# Dummy_Load.net
KiCad netlist of a schematic drawn in EAGLE
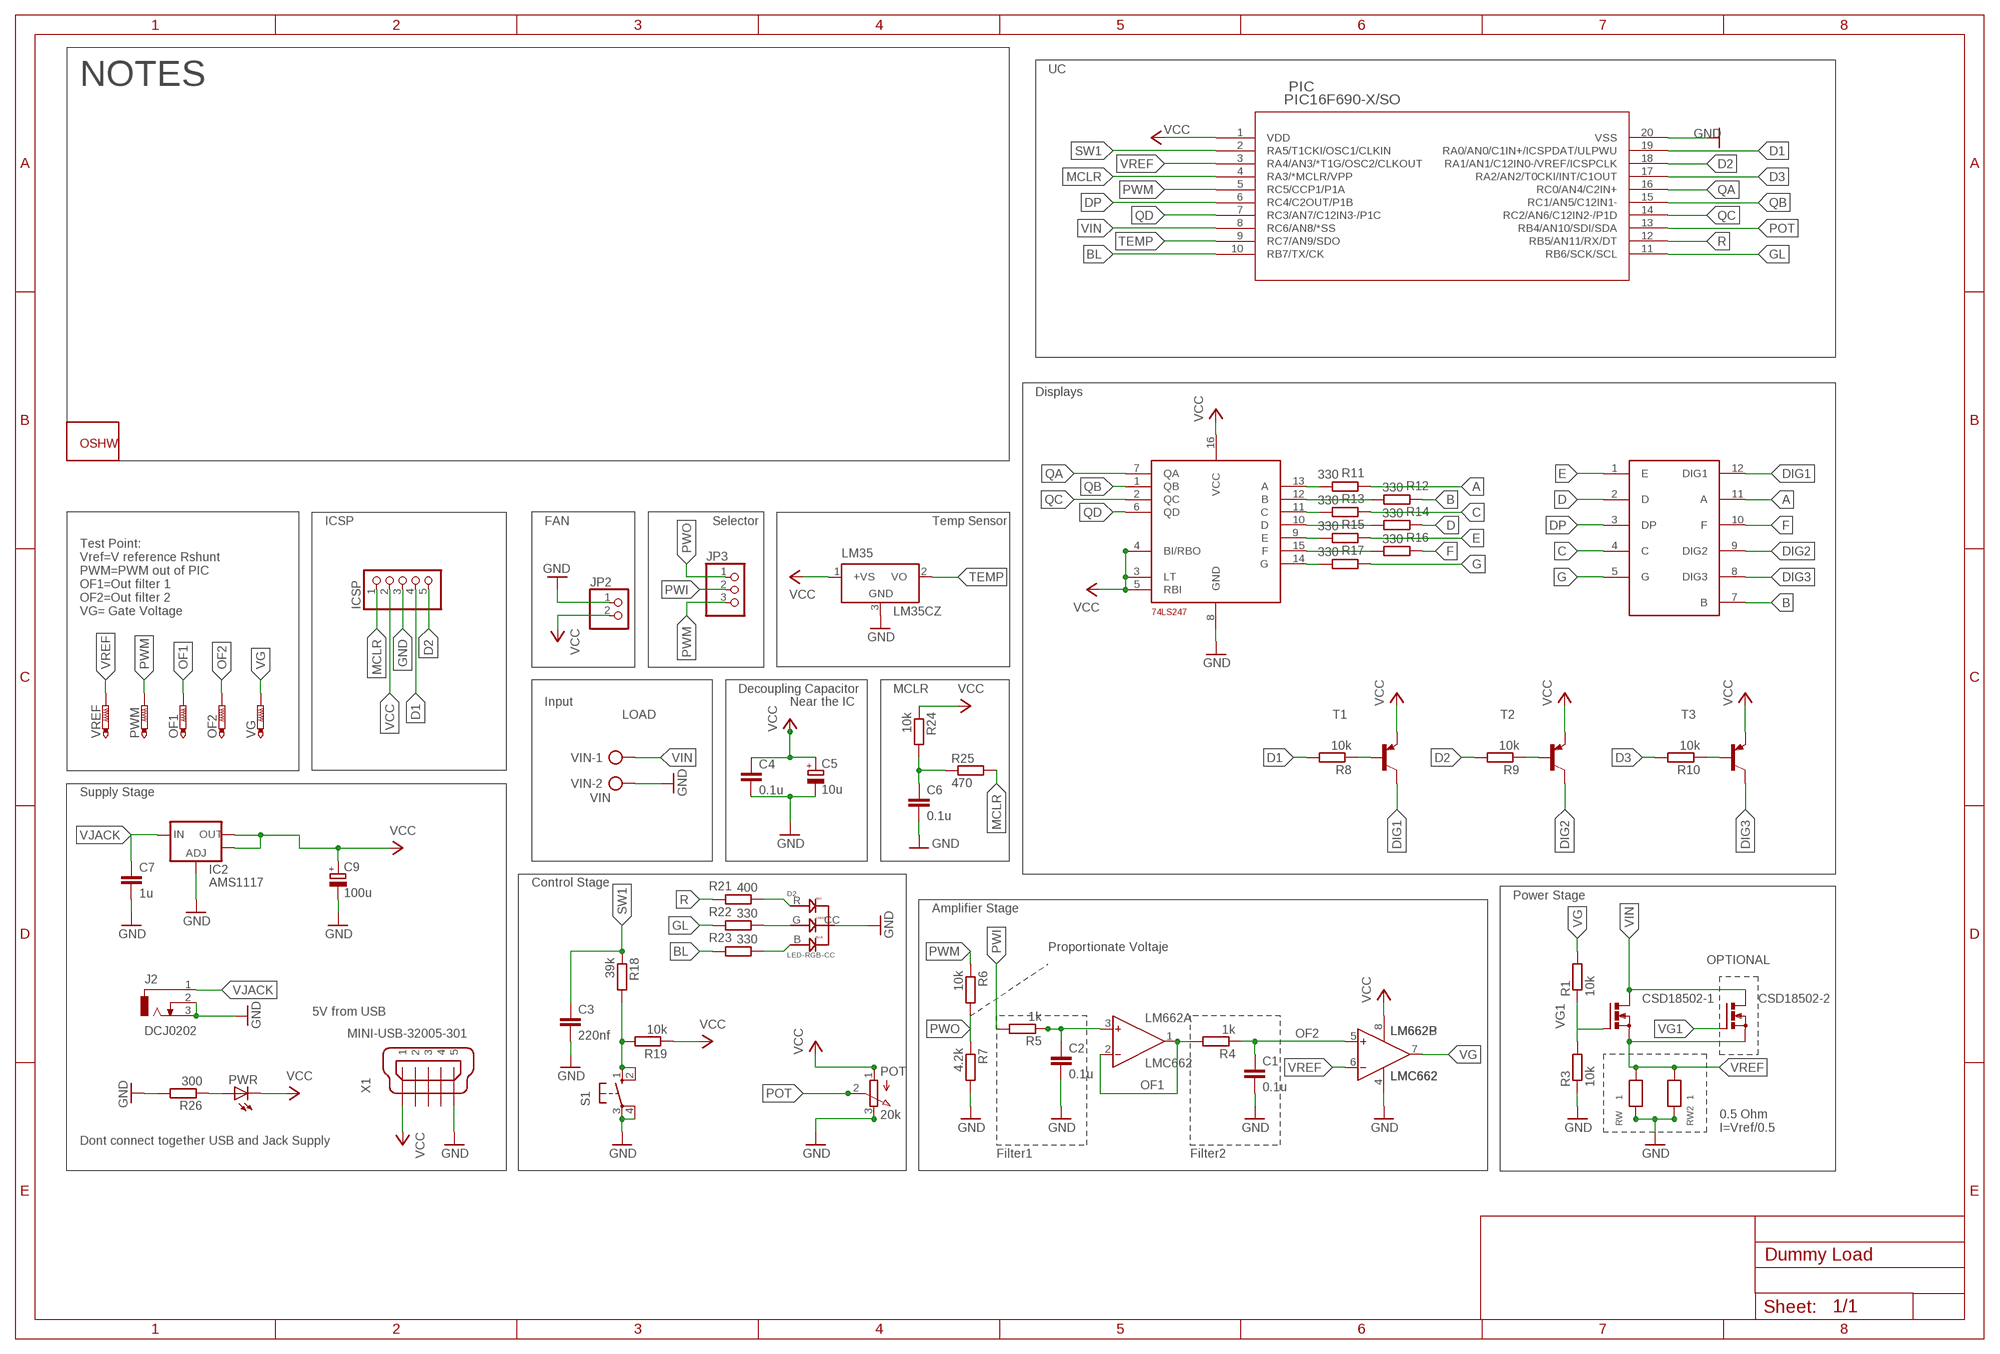
[diagram p0: schematic, sheet 1]

(export (version "E")
  (design (tool "Eeschema 10.0.6"))
  (components
    (comp (ref "74LS247")
      (value "BCD-7")
      (footprint "eagle-import:SOIC-16")
      (libsource (lib "eagle-import") (part "TLC5916/17"))
    )
    (comp (ref "C1")
      (value "0.1u")
      (footprint "eagle-import:C0805")
      (libsource (lib "eagle-import") (part "C-EUC0805"))
    )
    (comp (ref "C2")
      (value "0.1u")
      (footprint "eagle-import:C0805")
      (libsource (lib "eagle-import") (part "C-EUC0805"))
    )
    (comp (ref "C3")
      (value "220nf")
      (footprint "eagle-import:C0805")
      (libsource (lib "eagle-import") (part "C-EUC0805"))
    )
    (comp (ref "C4")
      (value "0.1u")
      (footprint "eagle-import:C0805")
      (libsource (lib "eagle-import") (part "C-EUC0805"))
    )
    (comp (ref "C5")
      (value "10u")
      (footprint "eagle-import:153CLV-0405")
      (libsource (lib "eagle-import") (part "CPOL-EU153CLV-0405"))
    )
    (comp (ref "C6")
      (value "0.1u")
      (footprint "eagle-import:C0805")
      (libsource (lib "eagle-import") (part "C-EUC0805"))
    )
    (comp (ref "C7")
      (value "1u")
      (footprint "eagle-import:C0805")
      (libsource (lib "eagle-import") (part "C-EUC0805"))
    )
    (comp (ref "C9")
      (value "100u")
      (footprint "eagle-import:153CLV-0605")
      (libsource (lib "eagle-import") (part "CPOL-EU153CLV-0605"))
    )
    (comp (ref "CSD18502-1")
      (value "PMOSFET_NTO220BV")
      (footprint "eagle-import:TO220BV")
      (libsource (lib "eagle-import") (part "PMOSFET_NTO220BV"))
    )
    (comp (ref "CSD18502-2")
      (value "PMOSFET_NTO220BV")
      (footprint "eagle-import:TO220BV")
      (libsource (lib "eagle-import") (part "PMOSFET_NTO220BV"))
    )
    (comp (ref "D2")
      (value "LED-RGB-CC")
      (footprint "eagle-import:LED-RGB-CC")
      (libsource (lib "eagle-import") (part "LED-RGB-CC"))
    )
    (comp (ref "DISPLAY")
      (value "7-SEGMENT--DIGITS")
      (footprint "eagle-import:7-SEGMENT--DIGITS")
      (libsource (lib "eagle-import") (part "7-SEGMENT--DIGITS"))
    )
    (comp (ref "GOLD_ORB_SM2")
      (value "OSHWLOGO_GOLD_ORB_MED")
      (footprint "eagle-import:OSHW1")
      (libsource (lib "eagle-import") (part "OSHWLOGO_GOLD_ORB_MED"))
    )
    (comp (ref "IC2")
      (value "AMS1117")
      (footprint "eagle-import:SOT223")
      (libsource (lib "eagle-import") (part "V_REG_LM1117SOT223"))
    )
    (comp (ref "ICSP")
      (value "PINHD-1X5")
      (footprint "eagle-import:1X05")
      (libsource (lib "eagle-import") (part "PINHD-1X5"))
    )
    (comp (ref "J2")
      (value "DCJ0202")
      (footprint "eagle-import:DCJ0202")
      (libsource (lib "eagle-import") (part "DCJ0202"))
    )
    (comp (ref "JP2")
      (value "PINHD-1X2")
      (footprint "eagle-import:1X02")
      (libsource (lib "eagle-import") (part "PINHD-1X2"))
    )
    (comp (ref "JP3")
      (value "PINHD-1X3")
      (footprint "eagle-import:1X03")
      (libsource (lib "eagle-import") (part "PINHD-1X3"))
    )
    (comp (ref "LM35")
      (value "LM35CZ")
      (footprint "eagle-import:TO92")
      (libsource (lib "eagle-import") (part "LM35CZ"))
    )
    (comp (ref "LM662")
      (value "LMC662")
      (footprint "eagle-import:SO8")
      (fields (field (name "MF") "ALTERA CORPORATION") (field (name "MPN") "AD8033ARZ"))
      (libsource (lib "eagle-import") (part "AD8033R"))
    )
    (comp (ref "OF1")
      (value "PTR1B1,27")
      (footprint "eagle-import:B1,27")
      (libsource (lib "eagle-import") (part "PTR1B1,27"))
    )
    (comp (ref "OF2")
      (value "PTR1B1,27")
      (footprint "eagle-import:B1,27")
      (libsource (lib "eagle-import") (part "PTR1B1,27"))
    )
    (comp (ref "PIC")
      (value "PIC16F690-X/SO")
      (footprint "eagle-import:SOIC20-W_MC")
      (libsource (lib "eagle-import") (part "PIC16F690-X/SO"))
    )
    (comp (ref "POT")
      (value "20k")
      (footprint "eagle-import:3RP_1610N")
      (libsource (lib "eagle-import") (part "3RP/1610N"))
    )
    (comp (ref "PWM")
      (value "PTR1B1,27")
      (footprint "eagle-import:B1,27")
      (libsource (lib "eagle-import") (part "PTR1B1,27"))
    )
    (comp (ref "PWR")
      (value "LEDCHIP-LED0805")
      (footprint "eagle-import:CHIP-LED0805")
      (libsource (lib "eagle-import") (part "LEDCHIP-LED0805"))
    )
    (comp (ref "R1")
      (value "10k")
      (footprint "eagle-import:R0805")
      (libsource (lib "eagle-import") (part "R-EU_R0805"))
    )
    (comp (ref "R3")
      (value "10k")
      (footprint "eagle-import:R0805")
      (libsource (lib "eagle-import") (part "R-EU_R0805"))
    )
    (comp (ref "R4")
      (value "1k")
      (footprint "eagle-import:R0805")
      (libsource (lib "eagle-import") (part "R-EU_R0805"))
    )
    (comp (ref "R5")
      (value "1k")
      (footprint "eagle-import:R0805")
      (libsource (lib "eagle-import") (part "R-EU_R0805"))
    )
    (comp (ref "R6")
      (value "10k")
      (footprint "eagle-import:R0805")
      (libsource (lib "eagle-import") (part "R-EU_R0805"))
    )
    (comp (ref "R7")
      (value "4.2k")
      (footprint "eagle-import:R0805")
      (libsource (lib "eagle-import") (part "R-EU_R0805"))
    )
    (comp (ref "R8")
      (value "10k")
      (footprint "eagle-import:R0805")
      (libsource (lib "eagle-import") (part "R-EU_R0805"))
    )
    (comp (ref "R9")
      (value "10k")
      (footprint "eagle-import:R0805")
      (libsource (lib "eagle-import") (part "R-EU_R0805"))
    )
    (comp (ref "R10")
      (value "10k")
      (footprint "eagle-import:R0805")
      (libsource (lib "eagle-import") (part "R-EU_R0805"))
    )
    (comp (ref "R11")
      (value "330")
      (footprint "eagle-import:R0805")
      (libsource (lib "eagle-import") (part "R-EU_R0805"))
    )
    (comp (ref "R12")
      (value "330")
      (footprint "eagle-import:R0805")
      (libsource (lib "eagle-import") (part "R-EU_R0805"))
    )
    (comp (ref "R13")
      (value "330")
      (footprint "eagle-import:R0805")
      (libsource (lib "eagle-import") (part "R-EU_R0805"))
    )
    (comp (ref "R14")
      (value "330")
      (footprint "eagle-import:R0805")
      (libsource (lib "eagle-import") (part "R-EU_R0805"))
    )
    (comp (ref "R15")
      (value "330")
      (footprint "eagle-import:R0805")
      (libsource (lib "eagle-import") (part "R-EU_R0805"))
    )
    (comp (ref "R16")
      (value "330")
      (footprint "eagle-import:R0805")
      (libsource (lib "eagle-import") (part "R-EU_R0805"))
    )
    (comp (ref "R17")
      (value "330")
      (footprint "eagle-import:R0805")
      (libsource (lib "eagle-import") (part "R-EU_R0805"))
    )
    (comp (ref "R18")
      (value "39k")
      (footprint "eagle-import:R0805")
      (libsource (lib "eagle-import") (part "R-EU_R0805"))
    )
    (comp (ref "R19")
      (value "10k")
      (footprint "eagle-import:R0805")
      (libsource (lib "eagle-import") (part "R-EU_R0805"))
    )
    (comp (ref "R21")
      (value "400")
      (footprint "eagle-import:R0805")
      (libsource (lib "eagle-import") (part "R-EU_R0805"))
    )
    (comp (ref "R22")
      (value "330")
      (footprint "eagle-import:R0805")
      (libsource (lib "eagle-import") (part "R-EU_R0805"))
    )
    (comp (ref "R23")
      (value "330")
      (footprint "eagle-import:R0805")
      (libsource (lib "eagle-import") (part "R-EU_R0805"))
    )
    (comp (ref "R24")
      (value "10k")
      (footprint "eagle-import:R0805")
      (libsource (lib "eagle-import") (part "R-EU_R0805"))
    )
    (comp (ref "R25")
      (value "470")
      (footprint "eagle-import:R0805")
      (libsource (lib "eagle-import") (part "R-EU_R0805"))
    )
    (comp (ref "R26")
      (value "300")
      (footprint "eagle-import:R0805")
      (libsource (lib "eagle-import") (part "R-EU_R0805"))
    )
    (comp (ref "RW")
      (value "1")
      (footprint "eagle-import:RESISTOR5W")
      (libsource (lib "eagle-import") (part "RESISTOR5W"))
    )
    (comp (ref "RW2")
      (value "1")
      (footprint "eagle-import:RESISTOR5W")
      (libsource (lib "eagle-import") (part "RESISTOR5W"))
    )
    (comp (ref "S1")
      (value "10-XX")
      (footprint "eagle-import:B3F-10XX")
      (fields (field (name "MPN") "B3F-1000"))
      (libsource (lib "eagle-import") (part "10-XX"))
    )
    (comp (ref "T1")
      (value "MMBT540LT1-PNP-SOT23-BEC")
      (footprint "eagle-import:SOT23-BEC")
      (libsource (lib "eagle-import") (part "-PNP-SOT23-BECMMBT540LT1"))
    )
    (comp (ref "T2")
      (value "MMBT540LT1-PNP-SOT23-BEC")
      (footprint "eagle-import:SOT23-BEC")
      (libsource (lib "eagle-import") (part "-PNP-SOT23-BECMMBT540LT1"))
    )
    (comp (ref "T3")
      (value "MMBT540LT1-PNP-SOT23-BEC")
      (footprint "eagle-import:SOT23-BEC")
      (libsource (lib "eagle-import") (part "-PNP-SOT23-BECMMBT540LT1"))
    )
    (comp (ref "VG")
      (value "PTR1B1,27")
      (footprint "eagle-import:B1,27")
      (libsource (lib "eagle-import") (part "PTR1B1,27"))
    )
    (comp (ref "VIN")
      (value "VIN")
      (footprint "eagle-import:AK500_2-H")
      (libsource (lib "eagle-import") (part "AK500/2-H"))
    )
    (comp (ref "VREF")
      (value "PTR1B1,27")
      (footprint "eagle-import:B1,27")
      (libsource (lib "eagle-import") (part "PTR1B1,27"))
    )
    (comp (ref "X1")
      (value "MINI-USB-32005-301")
      (footprint "eagle-import:32005-301")
      (libsource (lib "eagle-import") (part "MINI-USB-32005-301"))
    )
  )
  (nets
    (net (code "1") (name "A") (class "Default")
      (node (ref "DISPLAY") (pin "11") (pinfunction "A_11") (pintype "bidirectional"))
      (node (ref "R11") (pin "1") (pinfunction "1_1") (pintype "passive"))
    )
    (net (code "2") (name "B") (class "Default")
      (node (ref "DISPLAY") (pin "7") (pinfunction "B_7") (pintype "bidirectional"))
      (node (ref "R12") (pin "1") (pinfunction "1_1") (pintype "passive"))
    )
    (net (code "3") (name "BL") (class "Default")
      (node (ref "PIC") (pin "10") (pinfunction "RB7/TX/CK_10") (pintype "passive"))
      (node (ref "R23") (pin "2") (pinfunction "2_2") (pintype "passive"))
    )
    (net (code "4") (name "C") (class "Default")
      (node (ref "DISPLAY") (pin "4") (pinfunction "C_4") (pintype "bidirectional"))
      (node (ref "R13") (pin "1") (pinfunction "1_1") (pintype "passive"))
    )
    (net (code "5") (name "D") (class "Default")
      (node (ref "DISPLAY") (pin "2") (pinfunction "D_2") (pintype "bidirectional"))
      (node (ref "R14") (pin "1") (pinfunction "1_1") (pintype "passive"))
    )
    (net (code "6") (name "D1") (class "Default")
      (node (ref "ICSP") (pin "4") (pinfunction "4_4") (pintype "passive"))
      (node (ref "PIC") (pin "19") (pinfunction "RA0/AN0/C1IN+/ICSPDAT/ULPWU_19") (pintype "passive"))
      (node (ref "R8") (pin "2") (pinfunction "2_2") (pintype "passive"))
    )
    (net (code "7") (name "D2") (class "Default")
      (node (ref "ICSP") (pin "5") (pinfunction "5_5") (pintype "passive"))
      (node (ref "PIC") (pin "18") (pinfunction "RA1/AN1/C12IN0-/VREF/ICSPCLK_18") (pintype "passive"))
      (node (ref "R9") (pin "2") (pinfunction "2_2") (pintype "passive"))
    )
    (net (code "8") (name "D3") (class "Default")
      (node (ref "PIC") (pin "17") (pinfunction "RA2/AN2/T0CKI/INT/C1OUT_17") (pintype "passive"))
      (node (ref "R10") (pin "2") (pinfunction "2_2") (pintype "passive"))
    )
    (net (code "9") (name "DIG1") (class "Default")
      (node (ref "DISPLAY") (pin "12") (pinfunction "DIG1_12") (pintype "bidirectional"))
      (node (ref "T1") (pin "C") (pinfunction "C_C") (pintype "passive"))
    )
    (net (code "10") (name "DIG2") (class "Default")
      (node (ref "DISPLAY") (pin "9") (pinfunction "DIG2_9") (pintype "bidirectional"))
      (node (ref "T2") (pin "C") (pinfunction "C_C") (pintype "passive"))
    )
    (net (code "11") (name "DIG3") (class "Default")
      (node (ref "DISPLAY") (pin "8") (pinfunction "DIG3_8") (pintype "bidirectional"))
      (node (ref "T3") (pin "C") (pinfunction "C_C") (pintype "passive"))
    )
    (net (code "12") (name "DP") (class "Default")
      (node (ref "DISPLAY") (pin "3") (pinfunction "DP_3") (pintype "bidirectional"))
      (node (ref "PIC") (pin "6") (pinfunction "RC4/C2OUT/P1B_6") (pintype "passive"))
    )
    (net (code "13") (name "E") (class "Default")
      (node (ref "DISPLAY") (pin "1") (pinfunction "E_1") (pintype "bidirectional"))
      (node (ref "R15") (pin "1") (pinfunction "1_1") (pintype "passive"))
    )
    (net (code "14") (name "F") (class "Default")
      (node (ref "DISPLAY") (pin "10") (pinfunction "F_10") (pintype "bidirectional"))
      (node (ref "R16") (pin "1") (pinfunction "1_1") (pintype "passive"))
    )
    (net (code "15") (name "G") (class "Default")
      (node (ref "DISPLAY") (pin "5") (pinfunction "G_5") (pintype "bidirectional"))
      (node (ref "R17") (pin "1") (pinfunction "1_1") (pintype "passive"))
    )
    (net (code "16") (name "GL") (class "Default")
      (node (ref "PIC") (pin "11") (pinfunction "RB6/SCK/SCL_11") (pintype "passive"))
      (node (ref "R22") (pin "2") (pinfunction "2_2") (pintype "passive"))
    )
    (net (code "17") (name "GND") (class "Default")
      (node (ref "74LS247") (pin "8") (pinfunction "GND_8") (pintype "bidirectional"))
      (node (ref "C1") (pin "2") (pinfunction "2_2") (pintype "passive"))
      (node (ref "C2") (pin "2") (pinfunction "2_2") (pintype "passive"))
      (node (ref "C3") (pin "2") (pinfunction "2_2") (pintype "passive"))
      (node (ref "C4") (pin "2") (pinfunction "2_2") (pintype "passive"))
      (node (ref "C5") (pin "-") (pinfunction "-_-") (pintype "passive"))
      (node (ref "C6") (pin "2") (pinfunction "2_2") (pintype "passive"))
      (node (ref "C7") (pin "2") (pinfunction "2_2") (pintype "passive"))
      (node (ref "C9") (pin "-") (pinfunction "-_-") (pintype "passive"))
      (node (ref "D2") (pin "CC") (pinfunction "CC_CC") (pintype "bidirectional"))
      (node (ref "IC2") (pin "1") (pinfunction "ADJ_1") (pintype "input"))
      (node (ref "ICSP") (pin "3") (pinfunction "3_3") (pintype "passive"))
      (node (ref "J2") (pin "2") (pinfunction "2_2") (pintype "passive"))
      (node (ref "J2") (pin "3") (pinfunction "3_3") (pintype "passive"))
      (node (ref "JP2") (pin "1") (pinfunction "1_1") (pintype "passive"))
      (node (ref "LM35") (pin "3") (pinfunction "GND_3") (pintype "power_in"))
      (node (ref "LM662") (pin "4") (pinfunction "V-_4") (pintype "power_in"))
      (node (ref "PIC") (pin "20") (pinfunction "VSS_20") (pintype "passive"))
      (node (ref "POT") (pin "3") (pinfunction "E_3") (pintype "passive"))
      (node (ref "R26") (pin "2") (pinfunction "2_2") (pintype "passive"))
      (node (ref "R3") (pin "1") (pinfunction "1_1") (pintype "passive"))
      (node (ref "R7") (pin "2") (pinfunction "2_2") (pintype "passive"))
      (node (ref "RW") (pin "P$1") (pinfunction "1_P$1") (pintype "bidirectional"))
      (node (ref "RW2") (pin "P$1") (pinfunction "1_P$1") (pintype "bidirectional"))
      (node (ref "S1") (pin "3") (pinfunction "P_3") (pintype "passive"))
      (node (ref "S1") (pin "4") (pinfunction "P1_4") (pintype "passive"))
      (node (ref "VIN") (pin "2") (pinfunction "KL_2") (pintype "passive"))
      (node (ref "X1") (pin "5") (pinfunction "5_5") (pintype "passive"))
    )
    (net (code "18") (name "MCLR") (class "Default")
      (node (ref "ICSP") (pin "1") (pinfunction "1_1") (pintype "passive"))
      (node (ref "PIC") (pin "4") (pinfunction "RA3/*MCLR/VPP_4") (pintype "passive"))
      (node (ref "R25") (pin "2") (pinfunction "2_2") (pintype "passive"))
    )
    (net (code "19") (name "Net-(74LS247-A)") (class "Default")
      (node (ref "74LS247") (pin "13") (pinfunction "A_13") (pintype "bidirectional"))
      (node (ref "R11") (pin "2") (pinfunction "2_2") (pintype "passive"))
    )
    (net (code "20") (name "Net-(74LS247-B)") (class "Default")
      (node (ref "74LS247") (pin "12") (pinfunction "B_12") (pintype "bidirectional"))
      (node (ref "R12") (pin "2") (pinfunction "2_2") (pintype "passive"))
    )
    (net (code "21") (name "Net-(74LS247-C)") (class "Default")
      (node (ref "74LS247") (pin "11") (pinfunction "C_11") (pintype "bidirectional"))
      (node (ref "R13") (pin "2") (pinfunction "2_2") (pintype "passive"))
    )
    (net (code "22") (name "Net-(74LS247-D)") (class "Default")
      (node (ref "74LS247") (pin "10") (pinfunction "D_10") (pintype "bidirectional"))
      (node (ref "R14") (pin "2") (pinfunction "2_2") (pintype "passive"))
    )
    (net (code "23") (name "Net-(74LS247-E)") (class "Default")
      (node (ref "74LS247") (pin "9") (pinfunction "E_9") (pintype "bidirectional"))
      (node (ref "R15") (pin "2") (pinfunction "2_2") (pintype "passive"))
    )
    (net (code "24") (name "Net-(74LS247-F)") (class "Default")
      (node (ref "74LS247") (pin "15") (pinfunction "F_15") (pintype "bidirectional"))
      (node (ref "R16") (pin "2") (pinfunction "2_2") (pintype "passive"))
    )
    (net (code "25") (name "Net-(74LS247-G)") (class "Default")
      (node (ref "74LS247") (pin "14") (pinfunction "G_14") (pintype "bidirectional"))
      (node (ref "R17") (pin "2") (pinfunction "2_2") (pintype "passive"))
    )
    (net (code "26") (name "Net-(C6-Pad1)") (class "Default")
      (node (ref "C6") (pin "1") (pinfunction "1_1") (pintype "passive"))
      (node (ref "R24") (pin "2") (pinfunction "2_2") (pintype "passive"))
      (node (ref "R25") (pin "1") (pinfunction "1_1") (pintype "passive"))
    )
    (net (code "27") (name "Net-(D2-PadB)") (class "Default")
      (node (ref "D2") (pin "B") (pinfunction "B_B") (pintype "bidirectional"))
      (node (ref "R23") (pin "1") (pinfunction "1_1") (pintype "passive"))
    )
    (net (code "28") (name "Net-(D2-PadG)") (class "Default")
      (node (ref "D2") (pin "G") (pinfunction "G_G") (pintype "bidirectional"))
      (node (ref "R22") (pin "1") (pinfunction "1_1") (pintype "passive"))
    )
    (net (code "29") (name "Net-(D2-PadR)") (class "Default")
      (node (ref "D2") (pin "R") (pinfunction "R_R") (pintype "bidirectional"))
      (node (ref "R21") (pin "1") (pinfunction "1_1") (pintype "passive"))
    )
    (net (code "30") (name "Net-(LM662A-IN+)") (class "Default")
      (node (ref "C2") (pin "1") (pinfunction "1_1") (pintype "passive"))
      (node (ref "LM662") (pin "3") (pinfunction "IN+_3") (pintype "input"))
      (node (ref "R5") (pin "1") (pinfunction "1_1") (pintype "passive"))
    )
    (net (code "31") (name "Net-(PWR-PadA)") (class "Default")
      (node (ref "PWR") (pin "A") (pinfunction "A_A") (pintype "passive"))
      (node (ref "R26") (pin "1") (pinfunction "1_1") (pintype "passive"))
    )
    (net (code "32") (name "Net-(R8-Pad1)") (class "Default")
      (node (ref "R8") (pin "1") (pinfunction "1_1") (pintype "passive"))
      (node (ref "T1") (pin "B") (pinfunction "B_B") (pintype "passive"))
    )
    (net (code "33") (name "Net-(R9-Pad1)") (class "Default")
      (node (ref "R9") (pin "1") (pinfunction "1_1") (pintype "passive"))
      (node (ref "T2") (pin "B") (pinfunction "B_B") (pintype "passive"))
    )
    (net (code "34") (name "Net-(R10-Pad1)") (class "Default")
      (node (ref "R10") (pin "1") (pinfunction "1_1") (pintype "passive"))
      (node (ref "T3") (pin "B") (pinfunction "B_B") (pintype "passive"))
    )
    (net (code "35") (name "Net-(S1-S)") (class "Default")
      (node (ref "R18") (pin "2") (pinfunction "2_2") (pintype "passive"))
      (node (ref "R19") (pin "2") (pinfunction "2_2") (pintype "passive"))
      (node (ref "S1") (pin "1") (pinfunction "S_1") (pintype "passive"))
      (node (ref "S1") (pin "2") (pinfunction "S1_2") (pintype "passive"))
    )
    (net (code "36") (name "OF1") (class "Default")
      (node (ref "LM662") (pin "1") (pinfunction "OUT_1") (pintype "output"))
      (node (ref "LM662") (pin "2") (pinfunction "IN-_2") (pintype "input"))
      (node (ref "OF1") (pin "TP") (pinfunction "TP_TP") (pintype "input"))
      (node (ref "R4") (pin "2") (pinfunction "2_2") (pintype "passive"))
    )
    (net (code "37") (name "OF2") (class "Default")
      (node (ref "C1") (pin "1") (pinfunction "1_1") (pintype "passive"))
      (node (ref "LM662") (pin "5") (pinfunction "IN+_5") (pintype "input"))
      (node (ref "OF2") (pin "TP") (pinfunction "TP_TP") (pintype "input"))
      (node (ref "R4") (pin "1") (pinfunction "1_1") (pintype "passive"))
    )
    (net (code "38") (name "POT") (class "Default")
      (node (ref "PIC") (pin "13") (pinfunction "RB4/AN10/SDI/SDA_13") (pintype "passive"))
      (node (ref "POT") (pin "2") (pinfunction "S_2") (pintype "passive"))
    )
    (net (code "39") (name "PWI") (class "Default")
      (node (ref "JP3") (pin "2") (pinfunction "2_2") (pintype "passive"))
      (node (ref "R5") (pin "2") (pinfunction "2_2") (pintype "passive"))
    )
    (net (code "40") (name "PWM") (class "Default")
      (node (ref "JP3") (pin "3") (pinfunction "3_3") (pintype "passive"))
      (node (ref "PIC") (pin "5") (pinfunction "RC5/CCP1/P1A_5") (pintype "passive"))
      (node (ref "PWM") (pin "TP") (pinfunction "TP_TP") (pintype "input"))
      (node (ref "R6") (pin "1") (pinfunction "1_1") (pintype "passive"))
    )
    (net (code "41") (name "PWO") (class "Default")
      (node (ref "JP3") (pin "1") (pinfunction "1_1") (pintype "passive"))
      (node (ref "R6") (pin "2") (pinfunction "2_2") (pintype "passive"))
      (node (ref "R7") (pin "1") (pinfunction "1_1") (pintype "passive"))
    )
    (net (code "42") (name "QA") (class "Default")
      (node (ref "74LS247") (pin "7") (pinfunction "QA_7") (pintype "bidirectional"))
      (node (ref "PIC") (pin "16") (pinfunction "RC0/AN4/C2IN+_16") (pintype "passive"))
    )
    (net (code "43") (name "QB") (class "Default")
      (node (ref "74LS247") (pin "1") (pinfunction "QB_1") (pintype "bidirectional"))
      (node (ref "PIC") (pin "15") (pinfunction "RC1/AN5/C12IN1-_15") (pintype "passive"))
    )
    (net (code "44") (name "QC") (class "Default")
      (node (ref "74LS247") (pin "2") (pinfunction "QC_2") (pintype "bidirectional"))
      (node (ref "PIC") (pin "14") (pinfunction "RC2/AN6/C12IN2-/P1D_14") (pintype "passive"))
    )
    (net (code "45") (name "QD") (class "Default")
      (node (ref "74LS247") (pin "6") (pinfunction "QD_6") (pintype "bidirectional"))
      (node (ref "PIC") (pin "7") (pinfunction "RC3/AN7/C12IN3-/P1C_7") (pintype "passive"))
    )
    (net (code "46") (name "R") (class "Default")
      (node (ref "PIC") (pin "12") (pinfunction "RB5/AN11/RX/DT_12") (pintype "passive"))
      (node (ref "R21") (pin "2") (pinfunction "2_2") (pintype "passive"))
    )
    (net (code "47") (name "SW1") (class "Default")
      (node (ref "C3") (pin "1") (pinfunction "1_1") (pintype "passive"))
      (node (ref "PIC") (pin "2") (pinfunction "RA5/T1CKI/OSC1/CLKIN_2") (pintype "passive"))
      (node (ref "R18") (pin "1") (pinfunction "1_1") (pintype "passive"))
    )
    (net (code "48") (name "TEMP") (class "Default")
      (node (ref "LM35") (pin "2") (pinfunction "VO_2") (pintype "input"))
      (node (ref "PIC") (pin "9") (pinfunction "RC7/AN9/SDO_9") (pintype "passive"))
    )
    (net (code "49") (name "VCC") (class "Default")
      (node (ref "74LS247") (pin "16") (pinfunction "VCC_16") (pintype "bidirectional"))
      (node (ref "74LS247") (pin "3") (pinfunction "LT_3") (pintype "bidirectional"))
      (node (ref "74LS247") (pin "4") (pinfunction "BI/RBO_4") (pintype "bidirectional"))
      (node (ref "74LS247") (pin "5") (pinfunction "RBI_5") (pintype "bidirectional"))
      (node (ref "C4") (pin "1") (pinfunction "1_1") (pintype "passive"))
      (node (ref "C5") (pin "+") (pinfunction "+_+") (pintype "passive"))
      (node (ref "C9") (pin "+") (pinfunction "+_+") (pintype "passive"))
      (node (ref "IC2") (pin "2") (pinfunction "OUT_2") (pintype "output"))
      (node (ref "IC2") (pin "4") (pinfunction "OUT_4") (pintype "output"))
      (node (ref "ICSP") (pin "2") (pinfunction "2_2") (pintype "passive"))
      (node (ref "JP2") (pin "2") (pinfunction "2_2") (pintype "passive"))
      (node (ref "LM35") (pin "1") (pinfunction "+VS_1") (pintype "input"))
      (node (ref "LM662") (pin "8") (pinfunction "V+_8") (pintype "power_in"))
      (node (ref "PIC") (pin "1") (pinfunction "VDD_1") (pintype "passive"))
      (node (ref "POT") (pin "1") (pinfunction "A_1") (pintype "passive"))
      (node (ref "PWR") (pin "C") (pinfunction "C_C") (pintype "passive"))
      (node (ref "R19") (pin "1") (pinfunction "1_1") (pintype "passive"))
      (node (ref "R24") (pin "1") (pinfunction "1_1") (pintype "passive"))
      (node (ref "T1") (pin "E") (pinfunction "E_E") (pintype "passive"))
      (node (ref "T2") (pin "E") (pinfunction "E_E") (pintype "passive"))
      (node (ref "T3") (pin "E") (pinfunction "E_E") (pintype "passive"))
      (node (ref "X1") (pin "1") (pinfunction "1_1") (pintype "passive"))
    )
    (net (code "50") (name "VG") (class "Default")
      (node (ref "LM662") (pin "7") (pinfunction "OUT_7") (pintype "output"))
      (node (ref "R1") (pin "2") (pinfunction "2_2") (pintype "passive"))
      (node (ref "VG") (pin "TP") (pinfunction "TP_TP") (pintype "input"))
    )
    (net (code "51") (name "VG1") (class "Default")
      (node (ref "CSD18502-1") (pin "G") (pinfunction "G_G") (pintype "passive"))
      (node (ref "CSD18502-2") (pin "G") (pinfunction "G_G") (pintype "passive"))
      (node (ref "R1") (pin "1") (pinfunction "1_1") (pintype "passive"))
      (node (ref "R3") (pin "2") (pinfunction "2_2") (pintype "passive"))
    )
    (net (code "52") (name "VIN") (class "Default")
      (node (ref "CSD18502-1") (pin "D") (pinfunction "D_D") (pintype "passive"))
      (node (ref "CSD18502-2") (pin "D") (pinfunction "D_D") (pintype "passive"))
      (node (ref "PIC") (pin "8") (pinfunction "RC6/AN8/*SS_8") (pintype "passive"))
      (node (ref "VIN") (pin "1") (pinfunction "KL_1") (pintype "passive"))
    )
    (net (code "53") (name "VJACK") (class "Default")
      (node (ref "C7") (pin "1") (pinfunction "1_1") (pintype "passive"))
      (node (ref "IC2") (pin "3") (pinfunction "IN_3") (pintype "input"))
      (node (ref "J2") (pin "1") (pinfunction "1_1") (pintype "passive"))
    )
    (net (code "54") (name "VREF") (class "Default")
      (node (ref "CSD18502-1") (pin "S") (pinfunction "S_S") (pintype "passive"))
      (node (ref "CSD18502-2") (pin "S") (pinfunction "S_S") (pintype "passive"))
      (node (ref "LM662") (pin "6") (pinfunction "IN-_6") (pintype "input"))
      (node (ref "PIC") (pin "3") (pinfunction "RA4/AN3/*T1G/OSC2/CLKOUT_3") (pintype "passive"))
      (node (ref "RW") (pin "P$2") (pinfunction "2_P$2") (pintype "bidirectional"))
      (node (ref "RW2") (pin "P$2") (pinfunction "2_P$2") (pintype "bidirectional"))
      (node (ref "VREF") (pin "TP") (pinfunction "TP_TP") (pintype "input"))
    )
    (net (code "55") (name "unconnected-(X1-Pad2)") (class "Default")
      (node (ref "X1") (pin "2") (pinfunction "2_2") (pintype "passive"))
    )
    (net (code "56") (name "unconnected-(X1-Pad3)") (class "Default")
      (node (ref "X1") (pin "3") (pinfunction "3_3") (pintype "passive"))
    )
    (net (code "57") (name "unconnected-(X1-Pad4)") (class "Default")
      (node (ref "X1") (pin "4") (pinfunction "4_4") (pintype "passive"))
    )
  )
)
